# CLOCK.net
KiCad netlist of a schematic drawn in Altium Designer
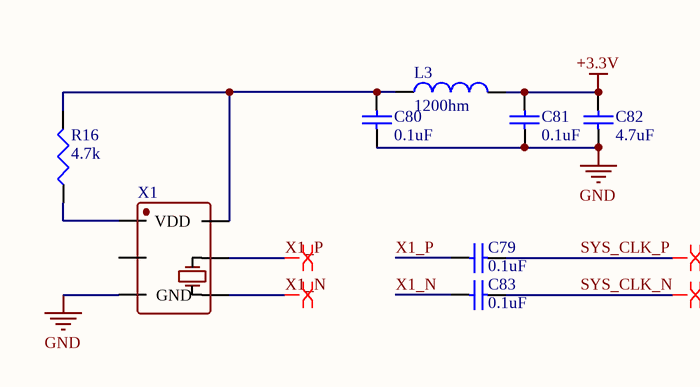
[diagram p0: CLOCK.SchDoc]

(export (version "E")
  (design (tool "Eeschema 10.0.6"))
  (components
    (comp (ref "C79")
      (value "0.1uF")
      (footprint "0402")
      (description "Capacitor (Semiconductor SIM Model)")
      (fields (field (name "Comment") "Cap Semi") (field (name "PUBLISHER") "Altium Limited"))
      (libsource (lib "Miscellaneous Devices") (part "Cap Semi"))
    )
    (comp (ref "C80")
      (value "0.1uF")
      (footprint "0402")
      (description "Capacitor (Semiconductor SIM Model)")
      (fields (field (name "Comment") "Cap Semi") (field (name "PUBLISHER") "Altium Limited"))
      (libsource (lib "Miscellaneous Devices") (part "Cap Semi"))
    )
    (comp (ref "C81")
      (value "0.1uF")
      (footprint "0402")
      (description "Capacitor (Semiconductor SIM Model)")
      (fields (field (name "Comment") "Cap Semi") (field (name "PUBLISHER") "Altium Limited"))
      (libsource (lib "Miscellaneous Devices") (part "Cap Semi"))
    )
    (comp (ref "C82")
      (value "4.7uF")
      (footprint "0402")
      (description "Capacitor (Semiconductor SIM Model)")
      (fields (field (name "Comment") "Cap Semi") (field (name "PUBLISHER") "Altium Limited"))
      (libsource (lib "Miscellaneous Devices") (part "Cap Semi"))
    )
    (comp (ref "C83")
      (value "0.1uF")
      (footprint "0402")
      (description "Capacitor (Semiconductor SIM Model)")
      (fields (field (name "Comment") "Cap Semi") (field (name "PUBLISHER") "Altium Limited"))
      (libsource (lib "Miscellaneous Devices") (part "Cap Semi"))
    )
    (comp (ref "L3")
      (value "1200hm")
      (footprint "0402-A")
      (description "Inductor")
      (fields (field (name "PUBLISHER") "Altium Limited"))
      (libsource (lib "Miscellaneous Devices") (part "Inductor"))
    )
    (comp (ref "R16")
      (value "4.7k")
      (footprint "J1-0603")
      (description "Resistor")
      (fields (field (name "Comment") "Res3") (field (name "PUBLISHER") "Altium Limited"))
      (libsource (lib "Miscellaneous Devices") (part "Res3"))
    )
    (comp (ref "X1") (value "晶振") (footprint "OSC6-5X7") (libsource (lib "Schlib1") (part "晶振")))
  )
  (nets
    (net (code "1") (name "+3.3V") (class "Default")
      (node (ref "C81") (pin "2") (pinfunction "2_2") (pintype "passive"))
      (node (ref "C82") (pin "2") (pinfunction "2_2") (pintype "passive"))
      (node (ref "L3") (pin "2") (pinfunction "2_2") (pintype "passive"))
    )
    (net (code "2") (name "/SYS_CLK_N") (class "Default")
      (node (ref "C83") (pin "2") (pinfunction "2_2") (pintype "passive"))
    )
    (net (code "3") (name "/SYS_CLK_P") (class "Default")
      (node (ref "C79") (pin "2") (pinfunction "2_2") (pintype "passive"))
    )
    (net (code "4") (name "/X1_N") (class "Default")
      (node (ref "C83") (pin "1") (pinfunction "1_1") (pintype "passive"))
      (node (ref "X1") (pin "4") (pinfunction "4_4") (pintype "passive"))
    )
    (net (code "5") (name "/X1_P") (class "Default")
      (node (ref "C79") (pin "1") (pinfunction "1_1") (pintype "passive"))
      (node (ref "X1") (pin "5") (pinfunction "5_5") (pintype "passive"))
    )
    (net (code "6") (name "GND") (class "Default")
      (node (ref "C80") (pin "1") (pinfunction "1_1") (pintype "passive"))
      (node (ref "C81") (pin "1") (pinfunction "1_1") (pintype "passive"))
      (node (ref "C82") (pin "1") (pinfunction "1_1") (pintype "passive"))
      (node (ref "X1") (pin "3") (pinfunction "GND_3") (pintype "passive"))
    )
    (net (code "7") (name "Net-(R16-Pad1)") (class "Default")
      (node (ref "R16") (pin "1") (pinfunction "1_1") (pintype "passive"))
      (node (ref "X1") (pin "1") (pinfunction "E/D_1") (pintype "passive"))
    )
    (net (code "8") (name "Net-(X1-VDD)") (class "Default")
      (node (ref "C80") (pin "2") (pinfunction "2_2") (pintype "passive"))
      (node (ref "L3") (pin "1") (pinfunction "1_1") (pintype "passive"))
      (node (ref "R16") (pin "2") (pinfunction "2_2") (pintype "passive"))
      (node (ref "X1") (pin "6") (pinfunction "VDD_6") (pintype "passive"))
    )
    (net (code "9") (name "unconnected-(X1-E{slash}D-Pad2)") (class "Default")
      (node (ref "X1") (pin "2") (pinfunction "E/D_2") (pintype "passive"))
    )
  )
)
